# Isolators.net
KiCad netlist of a schematic drawn in Altium Designer
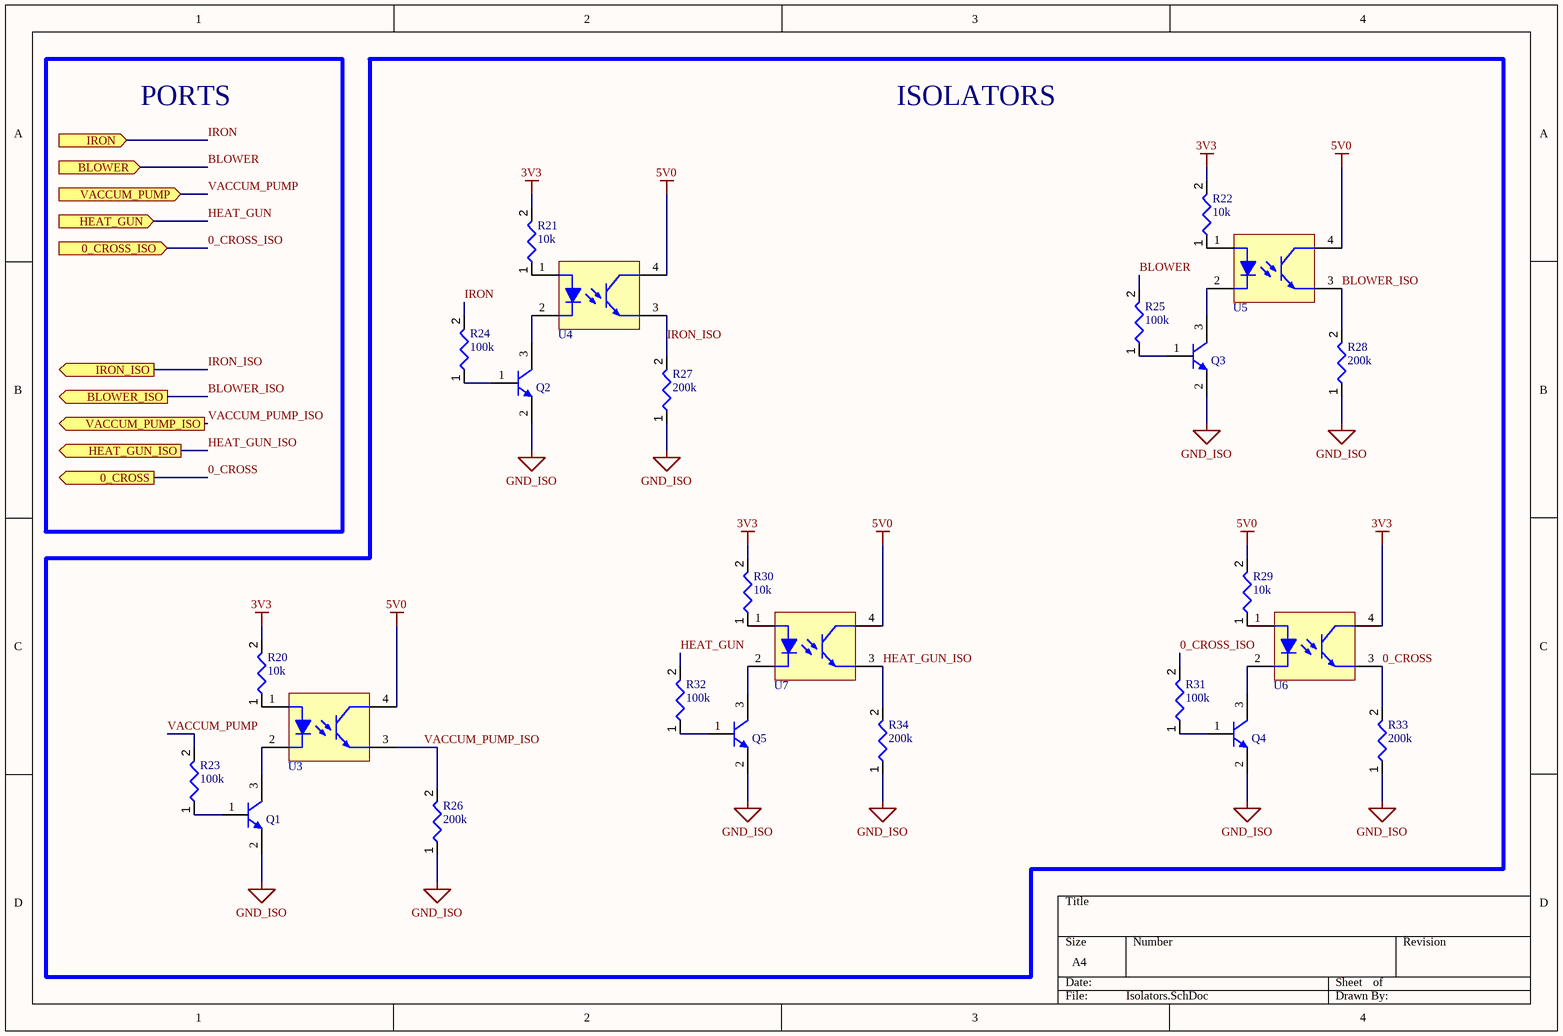
[diagram p0: Isolators.SchDoc]

(export (version "E")
  (design (tool "Eeschema 10.0.6"))
  (components
    (comp (ref "Q1")
      (value "SMMBT2222ALT1G")
      (footprint "ONSC-SOT-23-3-318-08_V")
      (description "General Purpose Transistor, NPN Silicon, 3-Pin SOT-23, Pb-Free, Tape and Reel")
      (fields (field (name "MANUFACTURER") "On Semiconductor"))
      (libsource (lib "Altium Content Vault") (part "ONSC-NPN-B1E2C3-3"))
    )
    (comp (ref "Q2")
      (value "SMMBT2222ALT1G")
      (footprint "ONSC-SOT-23-3-318-08_V")
      (description "General Purpose Transistor, NPN Silicon, 3-Pin SOT-23, Pb-Free, Tape and Reel")
      (fields (field (name "MANUFACTURER") "On Semiconductor"))
      (libsource (lib "Altium Content Vault") (part "ONSC-NPN-B1E2C3-3"))
    )
    (comp (ref "Q3")
      (value "SMMBT2222ALT1G")
      (footprint "ONSC-SOT-23-3-318-08_V")
      (description "General Purpose Transistor, NPN Silicon, 3-Pin SOT-23, Pb-Free, Tape and Reel")
      (fields (field (name "MANUFACTURER") "On Semiconductor"))
      (libsource (lib "Altium Content Vault") (part "ONSC-NPN-B1E2C3-3"))
    )
    (comp (ref "Q4")
      (value "SMMBT2222ALT1G")
      (footprint "ONSC-SOT-23-3-318-08_V")
      (description "General Purpose Transistor, NPN Silicon, 3-Pin SOT-23, Pb-Free, Tape and Reel")
      (fields (field (name "MANUFACTURER") "On Semiconductor"))
      (libsource (lib "Altium Content Vault") (part "ONSC-NPN-B1E2C3-3"))
    )
    (comp (ref "Q5")
      (value "SMMBT2222ALT1G")
      (footprint "ONSC-SOT-23-3-318-08_V")
      (description "General Purpose Transistor, NPN Silicon, 3-Pin SOT-23, Pb-Free, Tape and Reel")
      (fields (field (name "MANUFACTURER") "On Semiconductor"))
      (libsource (lib "Altium Content Vault") (part "ONSC-NPN-B1E2C3-3"))
    )
    (comp (ref "R20")
      (value "10k")
      (footprint "Generic_0603_RES")
      (fields
        (field (name "POWER") "100mW")
        (field (name "TOLERANCE") "1%")
        (field (name "Comment") "RES-TK_SMD-0603_VIS-CRCW_K_10K_1/10W_1%")
      )
      (libsource (lib "Paulo Peixoto") (part "Res"))
    )
    (comp (ref "R21")
      (value "10k")
      (footprint "Generic_0603_RES")
      (fields
        (field (name "POWER") "100mW")
        (field (name "TOLERANCE") "1%")
        (field (name "Comment") "RES-TK_SMD-0603_VIS-CRCW_K_10K_1/10W_1%")
      )
      (libsource (lib "Paulo Peixoto") (part "Res"))
    )
    (comp (ref "R22")
      (value "10k")
      (footprint "Generic_0603_RES")
      (fields
        (field (name "POWER") "100mW")
        (field (name "TOLERANCE") "1%")
        (field (name "Comment") "RES-TK_SMD-0603_VIS-CRCW_K_10K_1/10W_1%")
      )
      (libsource (lib "Paulo Peixoto") (part "Res"))
    )
    (comp (ref "R23")
      (value "100k")
      (footprint "Generic_0603_RES")
      (fields
        (field (name "POWER") "100mW")
        (field (name "TOLERANCE") "1%")
        (field (name "Comment") "RES-TK_SMD-0603_VIS-CRCW_K_100K_1/10W_1%")
      )
      (libsource (lib "Paulo Peixoto") (part "Res"))
    )
    (comp (ref "R24")
      (value "100k")
      (footprint "Generic_0603_RES")
      (fields
        (field (name "POWER") "100mW")
        (field (name "TOLERANCE") "1%")
        (field (name "Comment") "RES-TK_SMD-0603_VIS-CRCW_K_100K_1/10W_1%")
      )
      (libsource (lib "Paulo Peixoto") (part "Res"))
    )
    (comp (ref "R25")
      (value "100k")
      (footprint "Generic_0603_RES")
      (fields
        (field (name "POWER") "100mW")
        (field (name "TOLERANCE") "1%")
        (field (name "Comment") "RES-TK_SMD-0603_VIS-CRCW_K_100K_1/10W_1%")
      )
      (libsource (lib "Paulo Peixoto") (part "Res"))
    )
    (comp (ref "R26")
      (value "200k")
      (footprint "Generic_0603_RES")
      (fields
        (field (name "POWER") "100mW")
        (field (name "TOLERANCE") "1%")
        (field (name "Comment") "RES-TK_SMD-0603_VIS-CRCW_K_200K_1/10W_1%")
      )
      (libsource (lib "Paulo Peixoto") (part "Res"))
    )
    (comp (ref "R27")
      (value "200k")
      (footprint "Generic_0603_RES")
      (fields
        (field (name "POWER") "100mW")
        (field (name "TOLERANCE") "1%")
        (field (name "Comment") "RES-TK_SMD-0603_VIS-CRCW_K_200K_1/10W_1%")
      )
      (libsource (lib "Paulo Peixoto") (part "Res"))
    )
    (comp (ref "R28")
      (value "200k")
      (footprint "Generic_0603_RES")
      (fields
        (field (name "POWER") "100mW")
        (field (name "TOLERANCE") "1%")
        (field (name "Comment") "RES-TK_SMD-0603_VIS-CRCW_K_200K_1/10W_1%")
      )
      (libsource (lib "Paulo Peixoto") (part "Res"))
    )
    (comp (ref "R29")
      (value "10k")
      (footprint "Generic_0603_RES")
      (fields
        (field (name "POWER") "100mW")
        (field (name "TOLERANCE") "1%")
        (field (name "Comment") "RES-TK_SMD-0603_VIS-CRCW_K_10K_1/10W_1%")
      )
      (libsource (lib "Paulo Peixoto") (part "Res"))
    )
    (comp (ref "R30")
      (value "10k")
      (footprint "Generic_0603_RES")
      (fields
        (field (name "POWER") "100mW")
        (field (name "TOLERANCE") "1%")
        (field (name "Comment") "RES-TK_SMD-0603_VIS-CRCW_K_10K_1/10W_1%")
      )
      (libsource (lib "Paulo Peixoto") (part "Res"))
    )
    (comp (ref "R31")
      (value "100k")
      (footprint "Generic_0603_RES")
      (fields
        (field (name "POWER") "100mW")
        (field (name "TOLERANCE") "1%")
        (field (name "Comment") "RES-TK_SMD-0603_VIS-CRCW_K_100K_1/10W_1%")
      )
      (libsource (lib "Paulo Peixoto") (part "Res"))
    )
    (comp (ref "R32")
      (value "100k")
      (footprint "Generic_0603_RES")
      (fields
        (field (name "POWER") "100mW")
        (field (name "TOLERANCE") "1%")
        (field (name "Comment") "RES-TK_SMD-0603_VIS-CRCW_K_100K_1/10W_1%")
      )
      (libsource (lib "Paulo Peixoto") (part "Res"))
    )
    (comp (ref "R33")
      (value "200k")
      (footprint "Generic_0603_RES")
      (fields
        (field (name "POWER") "100mW")
        (field (name "TOLERANCE") "1%")
        (field (name "Comment") "RES-TK_SMD-0603_VIS-CRCW_K_200K_1/10W_1%")
      )
      (libsource (lib "Paulo Peixoto") (part "Res"))
    )
    (comp (ref "R34")
      (value "200k")
      (footprint "Generic_0603_RES")
      (fields
        (field (name "POWER") "100mW")
        (field (name "TOLERANCE") "1%")
        (field (name "Comment") "RES-TK_SMD-0603_VIS-CRCW_K_200K_1/10W_1%")
      )
      (libsource (lib "Paulo Peixoto") (part "Res"))
    )
    (comp (ref "U3")
      (value "H11A817ASD")
      (footprint "FAIR-H11A817ASD-4_V")
      (description "OptoCouplers & OptoIsolators Optocoupler SM-DIP4 Phototransistor")
      (libsource (lib "Paulo Peixoto") (part "FAIR-H11A817-4"))
    )
    (comp (ref "U4")
      (value "H11A817ASD")
      (footprint "FAIR-H11A817ASD-4_V")
      (description "OptoCouplers & OptoIsolators Optocoupler SM-DIP4 Phototransistor")
      (libsource (lib "Paulo Peixoto") (part "FAIR-H11A817-4"))
    )
    (comp (ref "U5")
      (value "H11A817ASD")
      (footprint "FAIR-H11A817ASD-4_V")
      (description "OptoCouplers & OptoIsolators Optocoupler SM-DIP4 Phototransistor")
      (libsource (lib "Paulo Peixoto") (part "FAIR-H11A817-4"))
    )
    (comp (ref "U6")
      (value "H11A817ASD")
      (footprint "FAIR-H11A817ASD-4_V")
      (description "OptoCouplers & OptoIsolators Optocoupler SM-DIP4 Phototransistor")
      (libsource (lib "Paulo Peixoto") (part "FAIR-H11A817-4"))
    )
    (comp (ref "U7")
      (value "H11A817ASD")
      (footprint "FAIR-H11A817ASD-4_V")
      (description "OptoCouplers & OptoIsolators Optocoupler SM-DIP4 Phototransistor")
      (libsource (lib "Paulo Peixoto") (part "FAIR-H11A817-4"))
    )
  )
  (nets
    (net (code "1") (name "/0_CROSS") (class "Default")
      (node (ref "R33") (pin "2") (pinfunction "2_2") (pintype "passive"))
      (node (ref "U6") (pin "3") (pinfunction "EMITTER_3") (pintype "passive"))
    )
    (net (code "2") (name "/0_CROSS_ISO") (class "Default")
      (node (ref "R31") (pin "2") (pinfunction "2_2") (pintype "passive"))
    )
    (net (code "3") (name "/BLOWER") (class "Default")
      (node (ref "R25") (pin "2") (pinfunction "2_2") (pintype "passive"))
    )
    (net (code "4") (name "/BLOWER_ISO") (class "Default")
      (node (ref "R28") (pin "2") (pinfunction "2_2") (pintype "passive"))
      (node (ref "U5") (pin "3") (pinfunction "EMITTER_3") (pintype "passive"))
    )
    (net (code "5") (name "/HEAT_GUN") (class "Default")
      (node (ref "R32") (pin "2") (pinfunction "2_2") (pintype "passive"))
    )
    (net (code "6") (name "/HEAT_GUN_ISO") (class "Default")
      (node (ref "R34") (pin "2") (pinfunction "2_2") (pintype "passive"))
      (node (ref "U7") (pin "3") (pinfunction "EMITTER_3") (pintype "passive"))
    )
    (net (code "7") (name "/IRON") (class "Default")
      (node (ref "R24") (pin "2") (pinfunction "2_2") (pintype "passive"))
    )
    (net (code "8") (name "/IRON_ISO") (class "Default")
      (node (ref "R27") (pin "2") (pinfunction "2_2") (pintype "passive"))
      (node (ref "U4") (pin "3") (pinfunction "EMITTER_3") (pintype "passive"))
    )
    (net (code "9") (name "/VACCUM_PUMP") (class "Default")
      (node (ref "R23") (pin "2") (pinfunction "2_2") (pintype "passive"))
    )
    (net (code "10") (name "/VACCUM_PUMP_ISO") (class "Default")
      (node (ref "R26") (pin "2") (pinfunction "2_2") (pintype "passive"))
      (node (ref "U3") (pin "3") (pinfunction "EMITTER_3") (pintype "passive"))
    )
    (net (code "11") (name "3V3") (class "Default")
      (node (ref "R20") (pin "2") (pinfunction "2_2") (pintype "passive"))
      (node (ref "R21") (pin "2") (pinfunction "2_2") (pintype "passive"))
      (node (ref "R22") (pin "2") (pinfunction "2_2") (pintype "passive"))
      (node (ref "R30") (pin "2") (pinfunction "2_2") (pintype "passive"))
      (node (ref "U6") (pin "4") (pinfunction "COLLECTOR_4") (pintype "passive"))
    )
    (net (code "12") (name "5V0") (class "Default")
      (node (ref "R29") (pin "2") (pinfunction "2_2") (pintype "passive"))
      (node (ref "U3") (pin "4") (pinfunction "COLLECTOR_4") (pintype "passive"))
      (node (ref "U4") (pin "4") (pinfunction "COLLECTOR_4") (pintype "passive"))
      (node (ref "U5") (pin "4") (pinfunction "COLLECTOR_4") (pintype "passive"))
      (node (ref "U7") (pin "4") (pinfunction "COLLECTOR_4") (pintype "passive"))
    )
    (net (code "13") (name "GND_ISO") (class "Default")
      (node (ref "Q1") (pin "2") (pinfunction "E_2") (pintype "passive"))
      (node (ref "Q2") (pin "2") (pinfunction "E_2") (pintype "passive"))
      (node (ref "Q3") (pin "2") (pinfunction "E_2") (pintype "passive"))
      (node (ref "Q4") (pin "2") (pinfunction "E_2") (pintype "passive"))
      (node (ref "Q5") (pin "2") (pinfunction "E_2") (pintype "passive"))
      (node (ref "R26") (pin "1") (pinfunction "1_1") (pintype "passive"))
      (node (ref "R27") (pin "1") (pinfunction "1_1") (pintype "passive"))
      (node (ref "R28") (pin "1") (pinfunction "1_1") (pintype "passive"))
      (node (ref "R33") (pin "1") (pinfunction "1_1") (pintype "passive"))
      (node (ref "R34") (pin "1") (pinfunction "1_1") (pintype "passive"))
    )
    (net (code "14") (name "Net-(Q1-B)") (class "Default")
      (node (ref "Q1") (pin "1") (pinfunction "B_1") (pintype "passive"))
      (node (ref "R23") (pin "1") (pinfunction "1_1") (pintype "passive"))
    )
    (net (code "15") (name "Net-(Q1-C)") (class "Default")
      (node (ref "Q1") (pin "3") (pinfunction "C_3") (pintype "passive"))
      (node (ref "U3") (pin "2") (pinfunction "CATHODE_2") (pintype "passive"))
    )
    (net (code "16") (name "Net-(Q2-B)") (class "Default")
      (node (ref "Q2") (pin "1") (pinfunction "B_1") (pintype "passive"))
      (node (ref "R24") (pin "1") (pinfunction "1_1") (pintype "passive"))
    )
    (net (code "17") (name "Net-(Q2-C)") (class "Default")
      (node (ref "Q2") (pin "3") (pinfunction "C_3") (pintype "passive"))
      (node (ref "U4") (pin "2") (pinfunction "CATHODE_2") (pintype "passive"))
    )
    (net (code "18") (name "Net-(Q3-B)") (class "Default")
      (node (ref "Q3") (pin "1") (pinfunction "B_1") (pintype "passive"))
      (node (ref "R25") (pin "1") (pinfunction "1_1") (pintype "passive"))
    )
    (net (code "19") (name "Net-(Q3-C)") (class "Default")
      (node (ref "Q3") (pin "3") (pinfunction "C_3") (pintype "passive"))
      (node (ref "U5") (pin "2") (pinfunction "CATHODE_2") (pintype "passive"))
    )
    (net (code "20") (name "Net-(Q4-B)") (class "Default")
      (node (ref "Q4") (pin "1") (pinfunction "B_1") (pintype "passive"))
      (node (ref "R31") (pin "1") (pinfunction "1_1") (pintype "passive"))
    )
    (net (code "21") (name "Net-(Q4-C)") (class "Default")
      (node (ref "Q4") (pin "3") (pinfunction "C_3") (pintype "passive"))
      (node (ref "U6") (pin "2") (pinfunction "CATHODE_2") (pintype "passive"))
    )
    (net (code "22") (name "Net-(Q5-B)") (class "Default")
      (node (ref "Q5") (pin "1") (pinfunction "B_1") (pintype "passive"))
      (node (ref "R32") (pin "1") (pinfunction "1_1") (pintype "passive"))
    )
    (net (code "23") (name "Net-(Q5-C)") (class "Default")
      (node (ref "Q5") (pin "3") (pinfunction "C_3") (pintype "passive"))
      (node (ref "U7") (pin "2") (pinfunction "CATHODE_2") (pintype "passive"))
    )
    (net (code "24") (name "Net-(U3-ANODE)") (class "Default")
      (node (ref "R20") (pin "1") (pinfunction "1_1") (pintype "passive"))
      (node (ref "U3") (pin "1") (pinfunction "ANODE_1") (pintype "passive"))
    )
    (net (code "25") (name "Net-(U4-ANODE)") (class "Default")
      (node (ref "R21") (pin "1") (pinfunction "1_1") (pintype "passive"))
      (node (ref "U4") (pin "1") (pinfunction "ANODE_1") (pintype "passive"))
    )
    (net (code "26") (name "Net-(U5-ANODE)") (class "Default")
      (node (ref "R22") (pin "1") (pinfunction "1_1") (pintype "passive"))
      (node (ref "U5") (pin "1") (pinfunction "ANODE_1") (pintype "passive"))
    )
    (net (code "27") (name "Net-(U6-ANODE)") (class "Default")
      (node (ref "R29") (pin "1") (pinfunction "1_1") (pintype "passive"))
      (node (ref "U6") (pin "1") (pinfunction "ANODE_1") (pintype "passive"))
    )
    (net (code "28") (name "Net-(U7-ANODE)") (class "Default")
      (node (ref "R30") (pin "1") (pinfunction "1_1") (pintype "passive"))
      (node (ref "U7") (pin "1") (pinfunction "ANODE_1") (pintype "passive"))
    )
  )
)
